# Nixie.net
KiCad netlist of a schematic drawn in Altium Designer
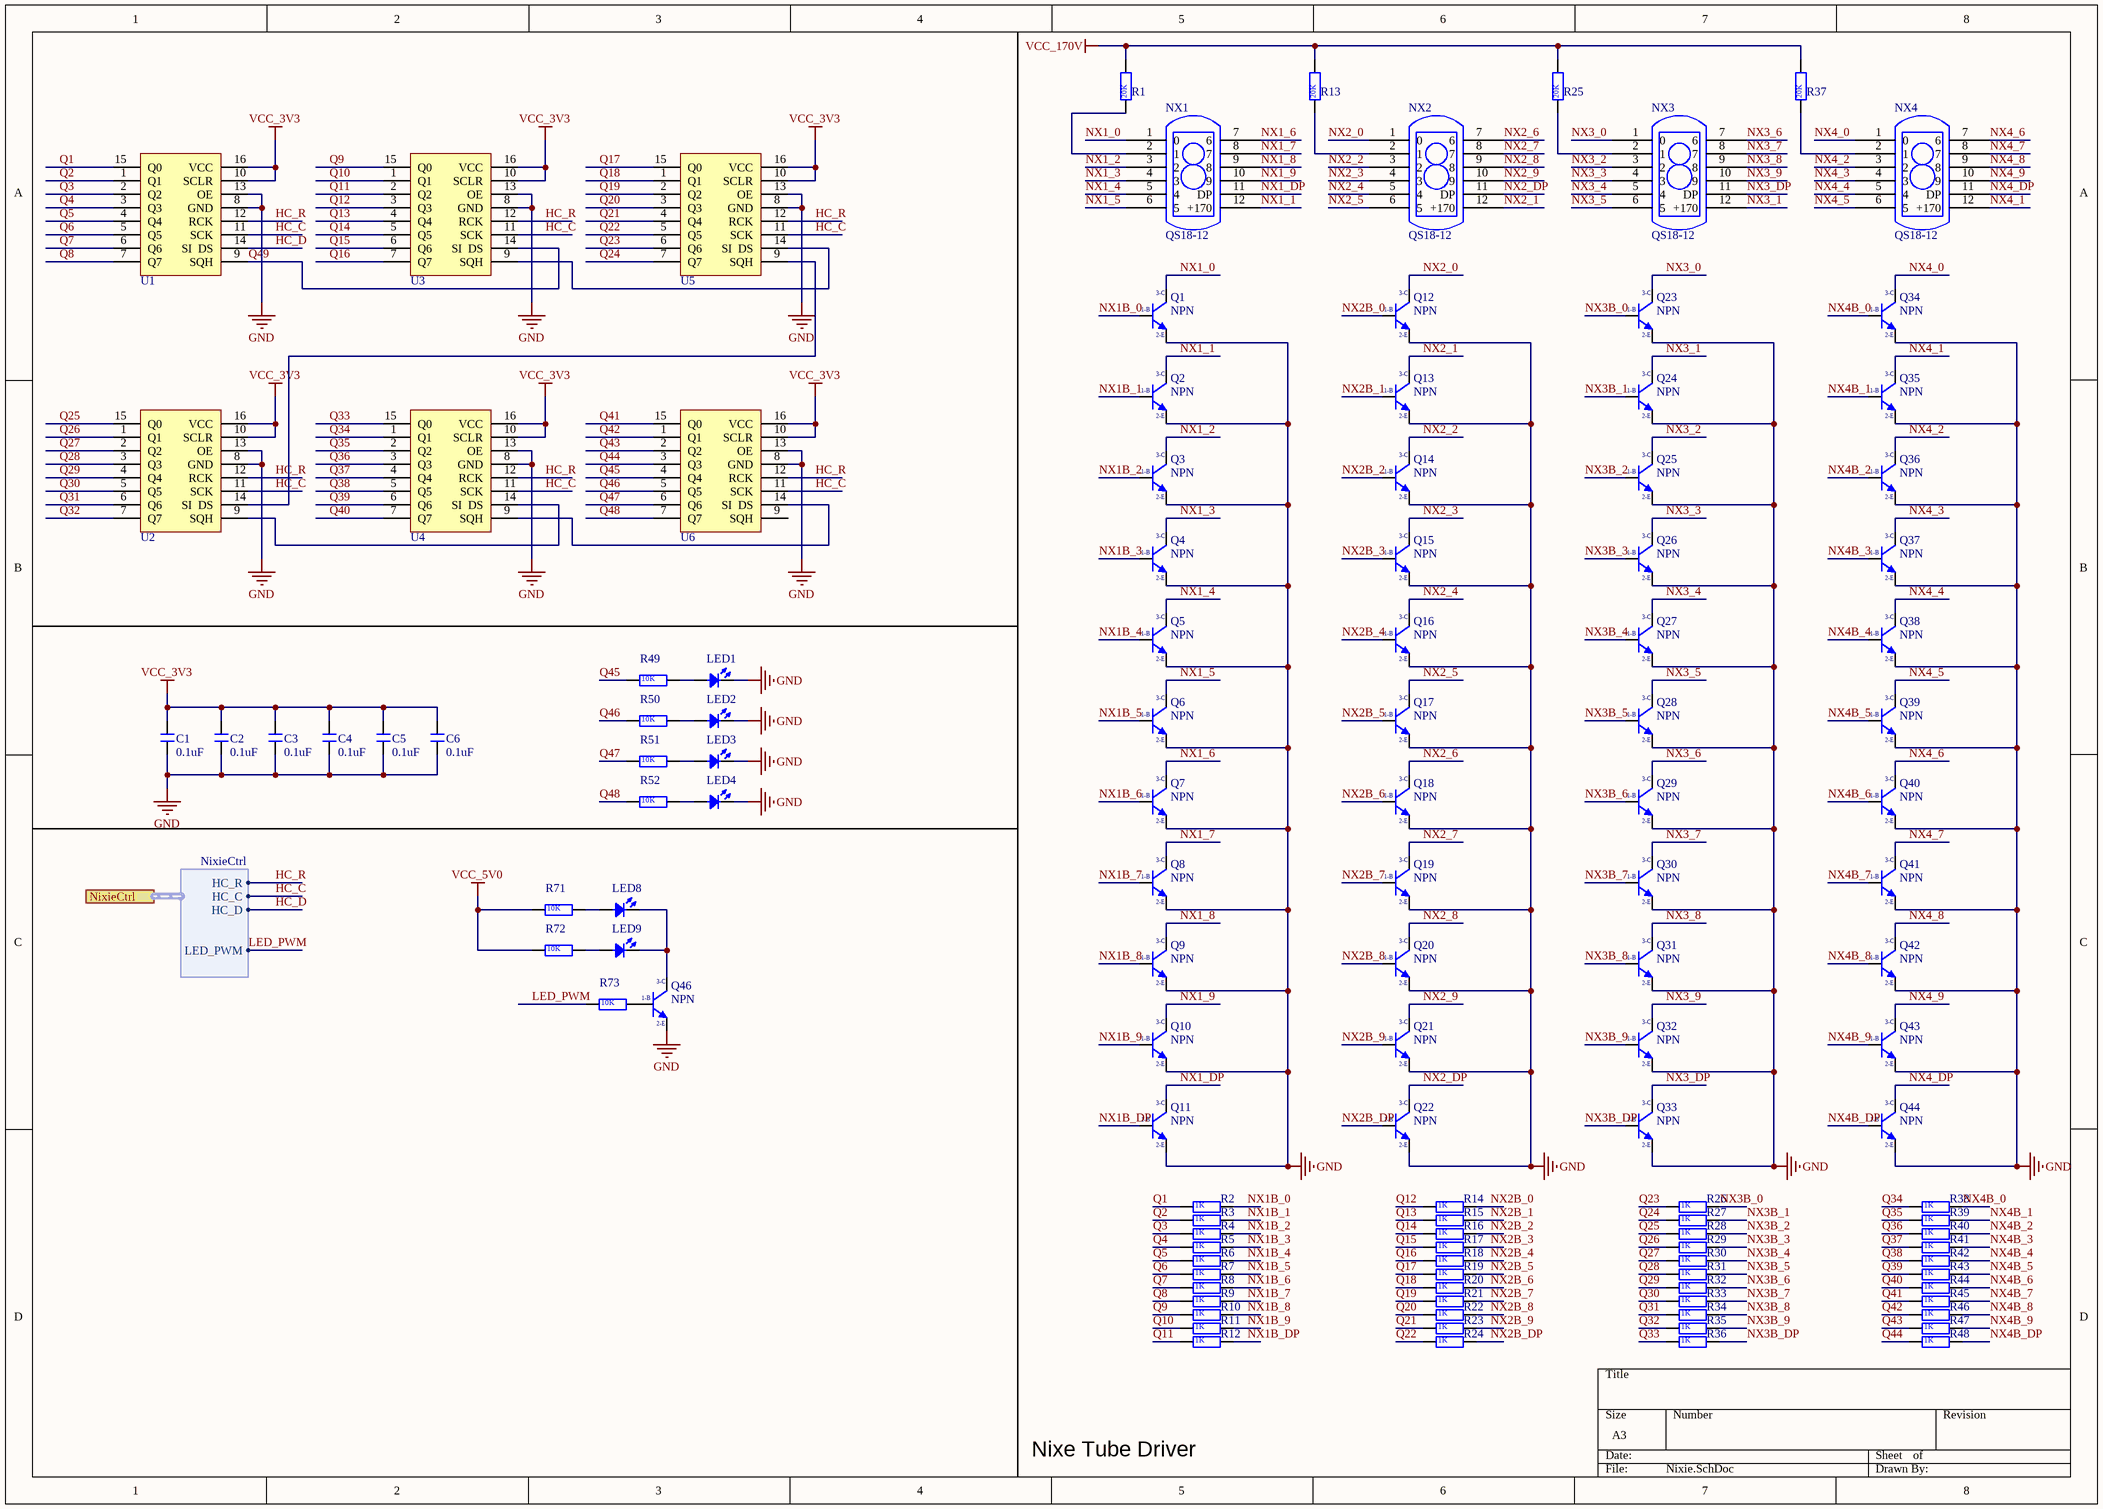
[diagram p0: Nixie.SchDoc]

(export (version "E")
  (design (tool "Eeschema 10.0.6"))
  (components
    (comp (ref "C1")
      (value "0.1uF")
      (footprint "C 0805")
      (description "无极性贴片电容")
      (fields (field (name "版权归属") "源创客"))
      (libsource (lib "电阻-电容-电感") (part "C"))
    )
    (comp (ref "C2")
      (value "0.1uF")
      (footprint "C 0805")
      (description "无极性贴片电容")
      (fields (field (name "版权归属") "源创客"))
      (libsource (lib "电阻-电容-电感") (part "C"))
    )
    (comp (ref "C3")
      (value "0.1uF")
      (footprint "C 0805")
      (description "无极性贴片电容")
      (fields (field (name "版权归属") "源创客"))
      (libsource (lib "电阻-电容-电感") (part "C"))
    )
    (comp (ref "C4")
      (value "0.1uF")
      (footprint "C 0805")
      (description "无极性贴片电容")
      (fields (field (name "版权归属") "源创客"))
      (libsource (lib "电阻-电容-电感") (part "C"))
    )
    (comp (ref "C5")
      (value "0.1uF")
      (footprint "C 0805")
      (description "无极性贴片电容")
      (fields (field (name "版权归属") "源创客"))
      (libsource (lib "电阻-电容-电感") (part "C"))
    )
    (comp (ref "C6")
      (value "0.1uF")
      (footprint "C 0805")
      (description "无极性贴片电容")
      (fields (field (name "版权归属") "源创客"))
      (libsource (lib "电阻-电容-电感") (part "C"))
    )
    (comp (ref "LED1")
      (value "LED")
      (footprint "0805D")
      (fields (field (name "PUBLISHER") "Altium Limited"))
      (libsource (lib "吴原理图库") (part "LED"))
    )
    (comp (ref "LED2")
      (value "LED")
      (footprint "0805D")
      (fields (field (name "PUBLISHER") "Altium Limited"))
      (libsource (lib "吴原理图库") (part "LED"))
    )
    (comp (ref "LED3")
      (value "LED")
      (footprint "0805D")
      (fields (field (name "PUBLISHER") "Altium Limited"))
      (libsource (lib "吴原理图库") (part "LED"))
    )
    (comp (ref "LED4")
      (value "LED")
      (footprint "0805D")
      (fields (field (name "PUBLISHER") "Altium Limited"))
      (libsource (lib "吴原理图库") (part "LED"))
    )
    (comp (ref "LED8")
      (value "LED")
      (footprint "LED 5MM-B")
      (fields (field (name "PUBLISHER") "Altium Limited"))
      (libsource (lib "吴原理图库") (part "LED"))
    )
    (comp (ref "LED9")
      (value "LED")
      (footprint "LED 5MM-B")
      (fields (field (name "PUBLISHER") "Altium Limited"))
      (libsource (lib "吴原理图库") (part "LED"))
    )
    (comp (ref "NX1")
      (value "QS18-12")
      (footprint "PCBComponent_1")
      (libsource (lib "Nixie") (part "QS18-12"))
    )
    (comp (ref "NX2")
      (value "QS18-12")
      (footprint "PCBComponent_1")
      (libsource (lib "Nixie") (part "QS18-12"))
    )
    (comp (ref "NX3")
      (value "QS18-12")
      (footprint "PCBComponent_1")
      (libsource (lib "Nixie") (part "QS18-12"))
    )
    (comp (ref "NX4")
      (value "QS18-12")
      (footprint "PCBComponent_1")
      (libsource (lib "Nixie") (part "QS18-12"))
    )
    (comp (ref "Q1") (value "NPN") (footprint "SOT-23") (libsource (lib "吴原理图库") (part "NPN-S8050-SOT-23")))
    (comp (ref "Q2") (value "NPN") (footprint "SOT-23") (libsource (lib "吴原理图库") (part "NPN-S8050-SOT-23")))
    (comp (ref "Q3") (value "NPN") (footprint "SOT-23") (libsource (lib "吴原理图库") (part "NPN-S8050-SOT-23")))
    (comp (ref "Q4") (value "NPN") (footprint "SOT-23") (libsource (lib "吴原理图库") (part "NPN-S8050-SOT-23")))
    (comp (ref "Q5") (value "NPN") (footprint "SOT-23") (libsource (lib "吴原理图库") (part "NPN-S8050-SOT-23")))
    (comp (ref "Q6") (value "NPN") (footprint "SOT-23") (libsource (lib "吴原理图库") (part "NPN-S8050-SOT-23")))
    (comp (ref "Q7") (value "NPN") (footprint "SOT-23") (libsource (lib "吴原理图库") (part "NPN-S8050-SOT-23")))
    (comp (ref "Q8") (value "NPN") (footprint "SOT-23") (libsource (lib "吴原理图库") (part "NPN-S8050-SOT-23")))
    (comp (ref "Q9") (value "NPN") (footprint "SOT-23") (libsource (lib "吴原理图库") (part "NPN-S8050-SOT-23")))
    (comp (ref "Q10") (value "NPN") (footprint "SOT-23") (libsource (lib "吴原理图库") (part "NPN-S8050-SOT-23")))
    (comp (ref "Q11") (value "NPN") (footprint "SOT-23") (libsource (lib "吴原理图库") (part "NPN-S8050-SOT-23")))
    (comp (ref "Q12") (value "NPN") (footprint "SOT-23") (libsource (lib "吴原理图库") (part "NPN-S8050-SOT-23")))
    (comp (ref "Q13") (value "NPN") (footprint "SOT-23") (libsource (lib "吴原理图库") (part "NPN-S8050-SOT-23")))
    (comp (ref "Q14") (value "NPN") (footprint "SOT-23") (libsource (lib "吴原理图库") (part "NPN-S8050-SOT-23")))
    (comp (ref "Q15") (value "NPN") (footprint "SOT-23") (libsource (lib "吴原理图库") (part "NPN-S8050-SOT-23")))
    (comp (ref "Q16") (value "NPN") (footprint "SOT-23") (libsource (lib "吴原理图库") (part "NPN-S8050-SOT-23")))
    (comp (ref "Q17") (value "NPN") (footprint "SOT-23") (libsource (lib "吴原理图库") (part "NPN-S8050-SOT-23")))
    (comp (ref "Q18") (value "NPN") (footprint "SOT-23") (libsource (lib "吴原理图库") (part "NPN-S8050-SOT-23")))
    (comp (ref "Q19") (value "NPN") (footprint "SOT-23") (libsource (lib "吴原理图库") (part "NPN-S8050-SOT-23")))
    (comp (ref "Q20") (value "NPN") (footprint "SOT-23") (libsource (lib "吴原理图库") (part "NPN-S8050-SOT-23")))
    (comp (ref "Q21") (value "NPN") (footprint "SOT-23") (libsource (lib "吴原理图库") (part "NPN-S8050-SOT-23")))
    (comp (ref "Q22") (value "NPN") (footprint "SOT-23") (libsource (lib "吴原理图库") (part "NPN-S8050-SOT-23")))
    (comp (ref "Q23") (value "NPN") (footprint "SOT-23") (libsource (lib "吴原理图库") (part "NPN-S8050-SOT-23")))
    (comp (ref "Q24") (value "NPN") (footprint "SOT-23") (libsource (lib "吴原理图库") (part "NPN-S8050-SOT-23")))
    (comp (ref "Q25") (value "NPN") (footprint "SOT-23") (libsource (lib "吴原理图库") (part "NPN-S8050-SOT-23")))
    (comp (ref "Q26") (value "NPN") (footprint "SOT-23") (libsource (lib "吴原理图库") (part "NPN-S8050-SOT-23")))
    (comp (ref "Q27") (value "NPN") (footprint "SOT-23") (libsource (lib "吴原理图库") (part "NPN-S8050-SOT-23")))
    (comp (ref "Q28") (value "NPN") (footprint "SOT-23") (libsource (lib "吴原理图库") (part "NPN-S8050-SOT-23")))
    (comp (ref "Q29") (value "NPN") (footprint "SOT-23") (libsource (lib "吴原理图库") (part "NPN-S8050-SOT-23")))
    (comp (ref "Q30") (value "NPN") (footprint "SOT-23") (libsource (lib "吴原理图库") (part "NPN-S8050-SOT-23")))
    (comp (ref "Q31") (value "NPN") (footprint "SOT-23") (libsource (lib "吴原理图库") (part "NPN-S8050-SOT-23")))
    (comp (ref "Q32") (value "NPN") (footprint "SOT-23") (libsource (lib "吴原理图库") (part "NPN-S8050-SOT-23")))
    (comp (ref "Q33") (value "NPN") (footprint "SOT-23") (libsource (lib "吴原理图库") (part "NPN-S8050-SOT-23")))
    (comp (ref "Q34") (value "NPN") (footprint "SOT-23") (libsource (lib "吴原理图库") (part "NPN-S8050-SOT-23")))
    (comp (ref "Q35") (value "NPN") (footprint "SOT-23") (libsource (lib "吴原理图库") (part "NPN-S8050-SOT-23")))
    (comp (ref "Q36") (value "NPN") (footprint "SOT-23") (libsource (lib "吴原理图库") (part "NPN-S8050-SOT-23")))
    (comp (ref "Q37") (value "NPN") (footprint "SOT-23") (libsource (lib "吴原理图库") (part "NPN-S8050-SOT-23")))
    (comp (ref "Q38") (value "NPN") (footprint "SOT-23") (libsource (lib "吴原理图库") (part "NPN-S8050-SOT-23")))
    (comp (ref "Q39") (value "NPN") (footprint "SOT-23") (libsource (lib "吴原理图库") (part "NPN-S8050-SOT-23")))
    (comp (ref "Q40") (value "NPN") (footprint "SOT-23") (libsource (lib "吴原理图库") (part "NPN-S8050-SOT-23")))
    (comp (ref "Q41") (value "NPN") (footprint "SOT-23") (libsource (lib "吴原理图库") (part "NPN-S8050-SOT-23")))
    (comp (ref "Q42") (value "NPN") (footprint "SOT-23") (libsource (lib "吴原理图库") (part "NPN-S8050-SOT-23")))
    (comp (ref "Q43") (value "NPN") (footprint "SOT-23") (libsource (lib "吴原理图库") (part "NPN-S8050-SOT-23")))
    (comp (ref "Q44") (value "NPN") (footprint "SOT-23") (libsource (lib "吴原理图库") (part "NPN-S8050-SOT-23")))
    (comp (ref "Q46") (value "NPN") (footprint "SOT-23") (libsource (lib "吴原理图库") (part "NPN-S8050-SOT-23")))
    (comp (ref "R1")
      (value "20K")
      (footprint "R 0603")
      (fields (field (name "Comment") "R"))
      (libsource (lib "") (part "R_1"))
    )
    (comp (ref "R2")
      (value "1K")
      (footprint "R 0603")
      (fields (field (name "Comment") "R"))
      (libsource (lib "吴原理图库") (part "R"))
    )
    (comp (ref "R3")
      (value "1K")
      (footprint "R 0603")
      (fields (field (name "Comment") "R"))
      (libsource (lib "吴原理图库") (part "R"))
    )
    (comp (ref "R4")
      (value "1K")
      (footprint "R 0603")
      (fields (field (name "Comment") "R"))
      (libsource (lib "吴原理图库") (part "R"))
    )
    (comp (ref "R5")
      (value "1K")
      (footprint "R 0603")
      (fields (field (name "Comment") "R"))
      (libsource (lib "吴原理图库") (part "R"))
    )
    (comp (ref "R6")
      (value "1K")
      (footprint "R 0603")
      (fields (field (name "Comment") "R"))
      (libsource (lib "吴原理图库") (part "R"))
    )
    (comp (ref "R7")
      (value "1K")
      (footprint "R 0603")
      (fields (field (name "Comment") "R"))
      (libsource (lib "吴原理图库") (part "R"))
    )
    (comp (ref "R8")
      (value "1K")
      (footprint "R 0603")
      (fields (field (name "Comment") "R"))
      (libsource (lib "吴原理图库") (part "R"))
    )
    (comp (ref "R9")
      (value "1K")
      (footprint "R 0603")
      (fields (field (name "Comment") "R"))
      (libsource (lib "吴原理图库") (part "R"))
    )
    (comp (ref "R10")
      (value "1K")
      (footprint "R 0603")
      (fields (field (name "Comment") "R"))
      (libsource (lib "吴原理图库") (part "R"))
    )
    (comp (ref "R11")
      (value "1K")
      (footprint "R 0603")
      (fields (field (name "Comment") "R"))
      (libsource (lib "吴原理图库") (part "R"))
    )
    (comp (ref "R12")
      (value "1K")
      (footprint "R 0603")
      (fields (field (name "Comment") "R"))
      (libsource (lib "吴原理图库") (part "R"))
    )
    (comp (ref "R13")
      (value "20K")
      (footprint "R 0603")
      (fields (field (name "Comment") "R"))
      (libsource (lib "") (part "R_1"))
    )
    (comp (ref "R14")
      (value "1K")
      (footprint "R 0603")
      (fields (field (name "Comment") "R"))
      (libsource (lib "吴原理图库") (part "R"))
    )
    (comp (ref "R15")
      (value "1K")
      (footprint "R 0603")
      (fields (field (name "Comment") "R"))
      (libsource (lib "吴原理图库") (part "R"))
    )
    (comp (ref "R16")
      (value "1K")
      (footprint "R 0603")
      (fields (field (name "Comment") "R"))
      (libsource (lib "吴原理图库") (part "R"))
    )
    (comp (ref "R17")
      (value "1K")
      (footprint "R 0603")
      (fields (field (name "Comment") "R"))
      (libsource (lib "吴原理图库") (part "R"))
    )
    (comp (ref "R18")
      (value "1K")
      (footprint "R 0603")
      (fields (field (name "Comment") "R"))
      (libsource (lib "吴原理图库") (part "R"))
    )
    (comp (ref "R19")
      (value "1K")
      (footprint "R 0603")
      (fields (field (name "Comment") "R"))
      (libsource (lib "吴原理图库") (part "R"))
    )
    (comp (ref "R20")
      (value "1K")
      (footprint "R 0603")
      (fields (field (name "Comment") "R"))
      (libsource (lib "吴原理图库") (part "R"))
    )
    (comp (ref "R21")
      (value "1K")
      (footprint "R 0603")
      (fields (field (name "Comment") "R"))
      (libsource (lib "吴原理图库") (part "R"))
    )
    (comp (ref "R22")
      (value "1K")
      (footprint "R 0603")
      (fields (field (name "Comment") "R"))
      (libsource (lib "吴原理图库") (part "R"))
    )
    (comp (ref "R23")
      (value "1K")
      (footprint "R 0603")
      (fields (field (name "Comment") "R"))
      (libsource (lib "吴原理图库") (part "R"))
    )
    (comp (ref "R24")
      (value "1K")
      (footprint "R 0603")
      (fields (field (name "Comment") "R"))
      (libsource (lib "吴原理图库") (part "R"))
    )
    (comp (ref "R25")
      (value "20K")
      (footprint "R 0603")
      (fields (field (name "Comment") "R"))
      (libsource (lib "") (part "R_1"))
    )
    (comp (ref "R26")
      (value "1K")
      (footprint "R 0603")
      (fields (field (name "Comment") "R"))
      (libsource (lib "吴原理图库") (part "R"))
    )
    (comp (ref "R27")
      (value "1K")
      (footprint "R 0603")
      (fields (field (name "Comment") "R"))
      (libsource (lib "吴原理图库") (part "R"))
    )
    (comp (ref "R28")
      (value "1K")
      (footprint "R 0603")
      (fields (field (name "Comment") "R"))
      (libsource (lib "吴原理图库") (part "R"))
    )
    (comp (ref "R29")
      (value "1K")
      (footprint "R 0603")
      (fields (field (name "Comment") "R"))
      (libsource (lib "吴原理图库") (part "R"))
    )
    (comp (ref "R30")
      (value "1K")
      (footprint "R 0603")
      (fields (field (name "Comment") "R"))
      (libsource (lib "吴原理图库") (part "R"))
    )
    (comp (ref "R31")
      (value "1K")
      (footprint "R 0603")
      (fields (field (name "Comment") "R"))
      (libsource (lib "吴原理图库") (part "R"))
    )
    (comp (ref "R32")
      (value "1K")
      (footprint "R 0603")
      (fields (field (name "Comment") "R"))
      (libsource (lib "吴原理图库") (part "R"))
    )
    (comp (ref "R33")
      (value "1K")
      (footprint "R 0603")
      (fields (field (name "Comment") "R"))
      (libsource (lib "吴原理图库") (part "R"))
    )
    (comp (ref "R34")
      (value "1K")
      (footprint "R 0603")
      (fields (field (name "Comment") "R"))
      (libsource (lib "吴原理图库") (part "R"))
    )
    (comp (ref "R35")
      (value "1K")
      (footprint "R 0603")
      (fields (field (name "Comment") "R"))
      (libsource (lib "吴原理图库") (part "R"))
    )
    (comp (ref "R36")
      (value "1K")
      (footprint "R 0603")
      (fields (field (name "Comment") "R"))
      (libsource (lib "吴原理图库") (part "R"))
    )
    (comp (ref "R37")
      (value "20K")
      (footprint "R 0603")
      (fields (field (name "Comment") "R"))
      (libsource (lib "") (part "R_1"))
    )
    (comp (ref "R38")
      (value "1K")
      (footprint "R 0603")
      (fields (field (name "Comment") "R"))
      (libsource (lib "吴原理图库") (part "R"))
    )
    (comp (ref "R39")
      (value "1K")
      (footprint "R 0603")
      (fields (field (name "Comment") "R"))
      (libsource (lib "吴原理图库") (part "R"))
    )
    (comp (ref "R40")
      (value "1K")
      (footprint "R 0603")
      (fields (field (name "Comment") "R"))
      (libsource (lib "吴原理图库") (part "R"))
    )
    (comp (ref "R41")
      (value "1K")
      (footprint "R 0603")
      (fields (field (name "Comment") "R"))
      (libsource (lib "吴原理图库") (part "R"))
    )
    (comp (ref "R42")
      (value "1K")
      (footprint "R 0603")
      (fields (field (name "Comment") "R"))
      (libsource (lib "吴原理图库") (part "R"))
    )
    (comp (ref "R43")
      (value "1K")
      (footprint "R 0603")
      (fields (field (name "Comment") "R"))
      (libsource (lib "吴原理图库") (part "R"))
    )
    (comp (ref "R44")
      (value "1K")
      (footprint "R 0603")
      (fields (field (name "Comment") "R"))
      (libsource (lib "吴原理图库") (part "R"))
    )
    (comp (ref "R45")
      (value "1K")
      (footprint "R 0603")
      (fields (field (name "Comment") "R"))
      (libsource (lib "吴原理图库") (part "R"))
    )
    (comp (ref "R46")
      (value "1K")
      (footprint "R 0603")
      (fields (field (name "Comment") "R"))
      (libsource (lib "吴原理图库") (part "R"))
    )
    (comp (ref "R47")
      (value "1K")
      (footprint "R 0603")
      (fields (field (name "Comment") "R"))
      (libsource (lib "吴原理图库") (part "R"))
    )
    (comp (ref "R48")
      (value "1K")
      (footprint "R 0603")
      (fields (field (name "Comment") "R"))
      (libsource (lib "吴原理图库") (part "R"))
    )
    (comp (ref "R49")
      (value "10K")
      (footprint "R 0603")
      (fields (field (name "Comment") "R"))
      (libsource (lib "吴原理图库") (part "R"))
    )
    (comp (ref "R50")
      (value "10K")
      (footprint "R 0603")
      (fields (field (name "Comment") "R"))
      (libsource (lib "吴原理图库") (part "R"))
    )
    (comp (ref "R51")
      (value "10K")
      (footprint "R 0603")
      (fields (field (name "Comment") "R"))
      (libsource (lib "吴原理图库") (part "R"))
    )
    (comp (ref "R52")
      (value "10K")
      (footprint "R 0603")
      (fields (field (name "Comment") "R"))
      (libsource (lib "吴原理图库") (part "R"))
    )
    (comp (ref "R71")
      (value "10K")
      (footprint "R 0603")
      (fields (field (name "Comment") "R"))
      (libsource (lib "吴原理图库") (part "R"))
    )
    (comp (ref "R72")
      (value "10K")
      (footprint "R 0603")
      (fields (field (name "Comment") "R"))
      (libsource (lib "吴原理图库") (part "R"))
    )
    (comp (ref "R73")
      (value "10K")
      (footprint "R 0603")
      (fields (field (name "Comment") "R"))
      (libsource (lib "吴原理图库") (part "R"))
    )
    (comp (ref "U1") (value "74HC595") (footprint "SOP16_M") (libsource (lib "吴原理图库") (part "74HC595_1")))
    (comp (ref "U2") (value "74HC595") (footprint "SOP16_M") (libsource (lib "吴原理图库") (part "74HC595_1")))
    (comp (ref "U3") (value "74HC595") (footprint "SOP16_M") (libsource (lib "吴原理图库") (part "74HC595_1")))
    (comp (ref "U4") (value "74HC595") (footprint "SOP16_M") (libsource (lib "吴原理图库") (part "74HC595_1")))
    (comp (ref "U5") (value "74HC595") (footprint "SOP16_M") (libsource (lib "吴原理图库") (part "74HC595_1")))
    (comp (ref "U6") (value "74HC595") (footprint "SOP16_M") (libsource (lib "吴原理图库") (part "74HC595_1")))
  )
  (nets
    (net (code "2") (name "/HC_C") (class "Default")
      (node (ref "U1") (pin "11") (pinfunction "SCK_11") (pintype "power_in"))
      (node (ref "U2") (pin "11") (pinfunction "SCK_11") (pintype "power_in"))
      (node (ref "U3") (pin "11") (pinfunction "SCK_11") (pintype "power_in"))
      (node (ref "U4") (pin "11") (pinfunction "SCK_11") (pintype "power_in"))
      (node (ref "U5") (pin "11") (pinfunction "SCK_11") (pintype "power_in"))
      (node (ref "U6") (pin "11") (pinfunction "SCK_11") (pintype "power_in"))
    )
    (net (code "3") (name "/HC_D") (class "Default")
      (node (ref "U1") (pin "14") (pinfunction "SI__DS_14") (pintype "power_in"))
    )
    (net (code "4") (name "/HC_R") (class "Default")
      (node (ref "U1") (pin "12") (pinfunction "RCK_12") (pintype "power_in"))
      (node (ref "U2") (pin "12") (pinfunction "RCK_12") (pintype "power_in"))
      (node (ref "U3") (pin "12") (pinfunction "RCK_12") (pintype "power_in"))
      (node (ref "U4") (pin "12") (pinfunction "RCK_12") (pintype "power_in"))
      (node (ref "U5") (pin "12") (pinfunction "RCK_12") (pintype "power_in"))
      (node (ref "U6") (pin "12") (pinfunction "RCK_12") (pintype "power_in"))
    )
    (net (code "5") (name "/LED_PWM") (class "Default")
      (node (ref "R73") (pin "1") (pinfunction "1_1") (pintype "passive"))
    )
    (net (code "6") (name "/NX1B_0") (class "Default")
      (node (ref "Q1") (pin "1") (pinfunction "B_1") (pintype "passive"))
      (node (ref "R2") (pin "2") (pinfunction "2_2") (pintype "passive"))
    )
    (net (code "7") (name "/NX1B_1") (class "Default")
      (node (ref "Q2") (pin "1") (pinfunction "B_1") (pintype "passive"))
      (node (ref "R3") (pin "2") (pinfunction "2_2") (pintype "passive"))
    )
    (net (code "8") (name "/NX1B_2") (class "Default")
      (node (ref "Q3") (pin "1") (pinfunction "B_1") (pintype "passive"))
      (node (ref "R4") (pin "2") (pinfunction "2_2") (pintype "passive"))
    )
    (net (code "9") (name "/NX1B_3") (class "Default")
      (node (ref "Q4") (pin "1") (pinfunction "B_1") (pintype "passive"))
      (node (ref "R5") (pin "2") (pinfunction "2_2") (pintype "passive"))
    )
    (net (code "10") (name "/NX1B_4") (class "Default")
      (node (ref "Q5") (pin "1") (pinfunction "B_1") (pintype "passive"))
      (node (ref "R6") (pin "2") (pinfunction "2_2") (pintype "passive"))
    )
    (net (code "11") (name "/NX1B_5") (class "Default")
      (node (ref "Q6") (pin "1") (pinfunction "B_1") (pintype "passive"))
      (node (ref "R7") (pin "2") (pinfunction "2_2") (pintype "passive"))
    )
    (net (code "12") (name "/NX1B_6") (class "Default")
      (node (ref "Q7") (pin "1") (pinfunction "B_1") (pintype "passive"))
      (node (ref "R8") (pin "2") (pinfunction "2_2") (pintype "passive"))
    )
    (net (code "13") (name "/NX1B_7") (class "Default")
      (node (ref "Q8") (pin "1") (pinfunction "B_1") (pintype "passive"))
      (node (ref "R9") (pin "2") (pinfunction "2_2") (pintype "passive"))
    )
    (net (code "14") (name "/NX1B_8") (class "Default")
      (node (ref "Q9") (pin "1") (pinfunction "B_1") (pintype "passive"))
      (node (ref "R10") (pin "2") (pinfunction "2_2") (pintype "passive"))
    )
    (net (code "15") (name "/NX1B_9") (class "Default")
      (node (ref "Q10") (pin "1") (pinfunction "B_1") (pintype "passive"))
      (node (ref "R11") (pin "2") (pinfunction "2_2") (pintype "passive"))
    )
    (net (code "16") (name "/NX1B_DP") (class "Default")
      (node (ref "Q11") (pin "1") (pinfunction "B_1") (pintype "passive"))
      (node (ref "R12") (pin "2") (pinfunction "2_2") (pintype "passive"))
    )
    (net (code "17") (name "/NX1_0") (class "Default")
      (node (ref "NX1") (pin "1") (pinfunction "0_1") (pintype "passive"))
      (node (ref "Q1") (pin "3") (pinfunction "C_3") (pintype "passive"))
    )
    (net (code "18") (name "/NX1_1") (class "Default")
      (node (ref "NX1") (pin "12") (pinfunction "+170_12") (pintype "passive"))
      (node (ref "Q2") (pin "3") (pinfunction "C_3") (pintype "passive"))
    )
    (net (code "19") (name "/NX1_2") (class "Default")
      (node (ref "NX1") (pin "3") (pinfunction "2_3") (pintype "passive"))
      (node (ref "Q3") (pin "3") (pinfunction "C_3") (pintype "passive"))
    )
    (net (code "20") (name "/NX1_3") (class "Default")
      (node (ref "NX1") (pin "4") (pinfunction "3_4") (pintype "passive"))
      (node (ref "Q4") (pin "3") (pinfunction "C_3") (pintype "passive"))
    )
    (net (code "21") (name "/NX1_4") (class "Default")
      (node (ref "NX1") (pin "5") (pinfunction "4_5") (pintype "passive"))
      (node (ref "Q5") (pin "3") (pinfunction "C_3") (pintype "passive"))
    )
    (net (code "22") (name "/NX1_5") (class "Default")
      (node (ref "NX1") (pin "6") (pinfunction "5_6") (pintype "passive"))
      (node (ref "Q6") (pin "3") (pinfunction "C_3") (pintype "passive"))
    )
    (net (code "23") (name "/NX1_6") (class "Default")
      (node (ref "NX1") (pin "7") (pinfunction "6_7") (pintype "passive"))
      (node (ref "Q7") (pin "3") (pinfunction "C_3") (pintype "passive"))
    )
    (net (code "24") (name "/NX1_7") (class "Default")
      (node (ref "NX1") (pin "8") (pinfunction "7_8") (pintype "passive"))
      (node (ref "Q8") (pin "3") (pinfunction "C_3") (pintype "passive"))
    )
    (net (code "25") (name "/NX1_8") (class "Default")
      (node (ref "NX1") (pin "9") (pinfunction "8_9") (pintype "passive"))
      (node (ref "Q9") (pin "3") (pinfunction "C_3") (pintype "passive"))
    )
    (net (code "26") (name "/NX1_9") (class "Default")
      (node (ref "NX1") (pin "10") (pinfunction "9_10") (pintype "passive"))
      (node (ref "Q10") (pin "3") (pinfunction "C_3") (pintype "passive"))
    )
    (net (code "27") (name "/NX1_DP") (class "Default")
      (node (ref "NX1") (pin "11") (pinfunction "DP_11") (pintype "passive"))
      (node (ref "Q11") (pin "3") (pinfunction "C_3") (pintype "passive"))
    )
    (net (code "28") (name "/NX2B_0") (class "Default")
      (node (ref "Q12") (pin "1") (pinfunction "B_1") (pintype "passive"))
      (node (ref "R14") (pin "2") (pinfunction "2_2") (pintype "passive"))
    )
    (net (code "29") (name "/NX2B_1") (class "Default")
      (node (ref "Q13") (pin "1") (pinfunction "B_1") (pintype "passive"))
      (node (ref "R15") (pin "2") (pinfunction "2_2") (pintype "passive"))
    )
    (net (code "30") (name "/NX2B_2") (class "Default")
      (node (ref "Q14") (pin "1") (pinfunction "B_1") (pintype "passive"))
      (node (ref "R16") (pin "2") (pinfunction "2_2") (pintype "passive"))
    )
    (net (code "31") (name "/NX2B_3") (class "Default")
      (node (ref "Q15") (pin "1") (pinfunction "B_1") (pintype "passive"))
      (node (ref "R17") (pin "2") (pinfunction "2_2") (pintype "passive"))
    )
    (net (code "32") (name "/NX2B_4") (class "Default")
      (node (ref "Q16") (pin "1") (pinfunction "B_1") (pintype "passive"))
      (node (ref "R18") (pin "2") (pinfunction "2_2") (pintype "passive"))
    )
    (net (code "33") (name "/NX2B_5") (class "Default")
      (node (ref "Q17") (pin "1") (pinfunction "B_1") (pintype "passive"))
      (node (ref "R19") (pin "2") (pinfunction "2_2") (pintype "passive"))
    )
    (net (code "34") (name "/NX2B_6") (class "Default")
      (node (ref "Q18") (pin "1") (pinfunction "B_1") (pintype "passive"))
      (node (ref "R20") (pin "2") (pinfunction "2_2") (pintype "passive"))
    )
    (net (code "35") (name "/NX2B_7") (class "Default")
      (node (ref "Q19") (pin "1") (pinfunction "B_1") (pintype "passive"))
      (node (ref "R21") (pin "2") (pinfunction "2_2") (pintype "passive"))
    )
    (net (code "36") (name "/NX2B_8") (class "Default")
      (node (ref "Q20") (pin "1") (pinfunction "B_1") (pintype "passive"))
      (node (ref "R22") (pin "2") (pinfunction "2_2") (pintype "passive"))
    )
    (net (code "37") (name "/NX2B_9") (class "Default")
      (node (ref "Q21") (pin "1") (pinfunction "B_1") (pintype "passive"))
      (node (ref "R23") (pin "2") (pinfunction "2_2") (pintype "passive"))
    )
    (net (code "38") (name "/NX2B_DP") (class "Default")
      (node (ref "Q22") (pin "1") (pinfunction "B_1") (pintype "passive"))
      (node (ref "R24") (pin "2") (pinfunction "2_2") (pintype "passive"))
    )
    (net (code "39") (name "/NX2_0") (class "Default")
      (node (ref "NX2") (pin "1") (pinfunction "0_1") (pintype "passive"))
      (node (ref "Q12") (pin "3") (pinfunction "C_3") (pintype "passive"))
    )
    (net (code "40") (name "/NX2_1") (class "Default")
      (node (ref "NX2") (pin "12") (pinfunction "+170_12") (pintype "passive"))
      (node (ref "Q13") (pin "3") (pinfunction "C_3") (pintype "passive"))
    )
    (net (code "41") (name "/NX2_2") (class "Default")
      (node (ref "NX2") (pin "3") (pinfunction "2_3") (pintype "passive"))
      (node (ref "Q14") (pin "3") (pinfunction "C_3") (pintype "passive"))
    )
    (net (code "42") (name "/NX2_3") (class "Default")
      (node (ref "NX2") (pin "4") (pinfunction "3_4") (pintype "passive"))
      (node (ref "Q15") (pin "3") (pinfunction "C_3") (pintype "passive"))
    )
    (net (code "43") (name "/NX2_4") (class "Default")
      (node (ref "NX2") (pin "5") (pinfunction "4_5") (pintype "passive"))
      (node (ref "Q16") (pin "3") (pinfunction "C_3") (pintype "passive"))
    )
    (net (code "44") (name "/NX2_5") (class "Default")
      (node (ref "NX2") (pin "6") (pinfunction "5_6") (pintype "passive"))
      (node (ref "Q17") (pin "3") (pinfunction "C_3") (pintype "passive"))
    )
    (net (code "45") (name "/NX2_6") (class "Default")
      (node (ref "NX2") (pin "7") (pinfunction "6_7") (pintype "passive"))
      (node (ref "Q18") (pin "3") (pinfunction "C_3") (pintype "passive"))
    )
    (net (code "46") (name "/NX2_7") (class "Default")
      (node (ref "NX2") (pin "8") (pinfunction "7_8") (pintype "passive"))
      (node (ref "Q19") (pin "3") (pinfunction "C_3") (pintype "passive"))
    )
    (net (code "47") (name "/NX2_8") (class "Default")
      (node (ref "NX2") (pin "9") (pinfunction "8_9") (pintype "passive"))
      (node (ref "Q20") (pin "3") (pinfunction "C_3") (pintype "passive"))
    )
    (net (code "48") (name "/NX2_9") (class "Default")
      (node (ref "NX2") (pin "10") (pinfunction "9_10") (pintype "passive"))
      (node (ref "Q21") (pin "3") (pinfunction "C_3") (pintype "passive"))
    )
    (net (code "49") (name "/NX2_DP") (class "Default")
      (node (ref "NX2") (pin "11") (pinfunction "DP_11") (pintype "passive"))
      (node (ref "Q22") (pin "3") (pinfunction "C_3") (pintype "passive"))
    )
    (net (code "50") (name "/NX3B_0") (class "Default")
      (node (ref "Q23") (pin "1") (pinfunction "B_1") (pintype "passive"))
      (node (ref "R26") (pin "2") (pinfunction "2_2") (pintype "passive"))
    )
    (net (code "51") (name "/NX3B_1") (class "Default")
      (node (ref "Q24") (pin "1") (pinfunction "B_1") (pintype "passive"))
      (node (ref "R27") (pin "2") (pinfunction "2_2") (pintype "passive"))
    )
    (net (code "52") (name "/NX3B_2") (class "Default")
      (node (ref "Q25") (pin "1") (pinfunction "B_1") (pintype "passive"))
      (node (ref "R28") (pin "2") (pinfunction "2_2") (pintype "passive"))
    )
    (net (code "53") (name "/NX3B_3") (class "Default")
      (node (ref "Q26") (pin "1") (pinfunction "B_1") (pintype "passive"))
      (node (ref "R29") (pin "2") (pinfunction "2_2") (pintype "passive"))
    )
    (net (code "54") (name "/NX3B_4") (class "Default")
      (node (ref "Q27") (pin "1") (pinfunction "B_1") (pintype "passive"))
      (node (ref "R30") (pin "2") (pinfunction "2_2") (pintype "passive"))
    )
    (net (code "55") (name "/NX3B_5") (class "Default")
      (node (ref "Q28") (pin "1") (pinfunction "B_1") (pintype "passive"))
      (node (ref "R31") (pin "2") (pinfunction "2_2") (pintype "passive"))
    )
    (net (code "56") (name "/NX3B_6") (class "Default")
      (node (ref "Q29") (pin "1") (pinfunction "B_1") (pintype "passive"))
      (node (ref "R32") (pin "2") (pinfunction "2_2") (pintype "passive"))
    )
    (net (code "57") (name "/NX3B_7") (class "Default")
      (node (ref "Q30") (pin "1") (pinfunction "B_1") (pintype "passive"))
      (node (ref "R33") (pin "2") (pinfunction "2_2") (pintype "passive"))
    )
    (net (code "58") (name "/NX3B_8") (class "Default")
      (node (ref "Q31") (pin "1") (pinfunction "B_1") (pintype "passive"))
      (node (ref "R34") (pin "2") (pinfunction "2_2") (pintype "passive"))
    )
    (net (code "59") (name "/NX3B_9") (class "Default")
      (node (ref "Q32") (pin "1") (pinfunction "B_1") (pintype "passive"))
      (node (ref "R35") (pin "2") (pinfunction "2_2") (pintype "passive"))
    )
    (net (code "60") (name "/NX3B_DP") (class "Default")
      (node (ref "Q33") (pin "1") (pinfunction "B_1") (pintype "passive"))
      (node (ref "R36") (pin "2") (pinfunction "2_2") (pintype "passive"))
    )
    (net (code "61") (name "/NX3_0") (class "Default")
      (node (ref "NX3") (pin "1") (pinfunction "0_1") (pintype "passive"))
      (node (ref "Q23") (pin "3") (pinfunction "C_3") (pintype "passive"))
    )
    (net (code "62") (name "/NX3_1") (class "Default")
      (node (ref "NX3") (pin "12") (pinfunction "+170_12") (pintype "passive"))
      (node (ref "Q24") (pin "3") (pinfunction "C_3") (pintype "passive"))
    )
    (net (code "63") (name "/NX3_2") (class "Default")
      (node (ref "NX3") (pin "3") (pinfunction "2_3") (pintype "passive"))
      (node (ref "Q25") (pin "3") (pinfunction "C_3") (pintype "passive"))
    )
    (net (code "64") (name "/NX3_3") (class "Default")
      (node (ref "NX3") (pin "4") (pinfunction "3_4") (pintype "passive"))
      (node (ref "Q26") (pin "3") (pinfunction "C_3") (pintype "passive"))
    )
    (net (code "65") (name "/NX3_4") (class "Default")
      (node (ref "NX3") (pin "5") (pinfunction "4_5") (pintype "passive"))
      (node (ref "Q27") (pin "3") (pinfunction "C_3") (pintype "passive"))
    )
    (net (code "66") (name "/NX3_5") (class "Default")
      (node (ref "NX3") (pin "6") (pinfunction "5_6") (pintype "passive"))
      (node (ref "Q28") (pin "3") (pinfunction "C_3") (pintype "passive"))
    )
    (net (code "67") (name "/NX3_6") (class "Default")
      (node (ref "NX3") (pin "7") (pinfunction "6_7") (pintype "passive"))
      (node (ref "Q29") (pin "3") (pinfunction "C_3") (pintype "passive"))
    )
    (net (code "68") (name "/NX3_7") (class "Default")
      (node (ref "NX3") (pin "8") (pinfunction "7_8") (pintype "passive"))
      (node (ref "Q30") (pin "3") (pinfunction "C_3") (pintype "passive"))
    )
    (net (code "69") (name "/NX3_8") (class "Default")
      (node (ref "NX3") (pin "9") (pinfunction "8_9") (pintype "passive"))
      (node (ref "Q31") (pin "3") (pinfunction "C_3") (pintype "passive"))
    )
    (net (code "70") (name "/NX3_9") (class "Default")
      (node (ref "NX3") (pin "10") (pinfunction "9_10") (pintype "passive"))
      (node (ref "Q32") (pin "3") (pinfunction "C_3") (pintype "passive"))
    )
    (net (code "71") (name "/NX3_DP") (class "Default")
      (node (ref "NX3") (pin "11") (pinfunction "DP_11") (pintype "passive"))
      (node (ref "Q33") (pin "3") (pinfunction "C_3") (pintype "passive"))
    )
    (net (code "72") (name "/NX4B_0") (class "Default")
      (node (ref "Q34") (pin "1") (pinfunction "B_1") (pintype "passive"))
      (node (ref "R38") (pin "2") (pinfunction "2_2") (pintype "passive"))
    )
    (net (code "73") (name "/NX4B_1") (class "Default")
      (node (ref "Q35") (pin "1") (pinfunction "B_1") (pintype "passive"))
      (node (ref "R39") (pin "2") (pinfunction "2_2") (pintype "passive"))
    )
    (net (code "74") (name "/NX4B_2") (class "Default")
      (node (ref "Q36") (pin "1") (pinfunction "B_1") (pintype "passive"))
      (node (ref "R40") (pin "2") (pinfunction "2_2") (pintype "passive"))
    )
    (net (code "75") (name "/NX4B_3") (class "Default")
      (node (ref "Q37") (pin "1") (pinfunction "B_1") (pintype "passive"))
      (node (ref "R41") (pin "2") (pinfunction "2_2") (pintype "passive"))
    )
    (net (code "76") (name "/NX4B_4") (class "Default")
      (node (ref "Q38") (pin "1") (pinfunction "B_1") (pintype "passive"))
      (node (ref "R42") (pin "2") (pinfunction "2_2") (pintype "passive"))
    )
    (net (code "77") (name "/NX4B_5") (class "Default")
      (node (ref "Q39") (pin "1") (pinfunction "B_1") (pintype "passive"))
      (node (ref "R43") (pin "2") (pinfunction "2_2") (pintype "passive"))
    )
    (net (code "78") (name "/NX4B_6") (class "Default")
      (node (ref "Q40") (pin "1") (pinfunction "B_1") (pintype "passive"))
      (node (ref "R44") (pin "2") (pinfunction "2_2") (pintype "passive"))
    )
    (net (code "79") (name "/NX4B_7") (class "Default")
      (node (ref "Q41") (pin "1") (pinfunction "B_1") (pintype "passive"))
      (node (ref "R45") (pin "2") (pinfunction "2_2") (pintype "passive"))
    )
    (net (code "80") (name "/NX4B_8") (class "Default")
      (node (ref "Q42") (pin "1") (pinfunction "B_1") (pintype "passive"))
      (node (ref "R46") (pin "2") (pinfunction "2_2") (pintype "passive"))
    )
    (net (code "81") (name "/NX4B_9") (class "Default")
      (node (ref "Q43") (pin "1") (pinfunction "B_1") (pintype "passive"))
      (node (ref "R47") (pin "2") (pinfunction "2_2") (pintype "passive"))
    )
    (net (code "82") (name "/NX4B_DP") (class "Default")
      (node (ref "Q44") (pin "1") (pinfunction "B_1") (pintype "passive"))
      (node (ref "R48") (pin "2") (pinfunction "2_2") (pintype "passive"))
    )
    (net (code "83") (name "/NX4_0") (class "Default")
      (node (ref "NX4") (pin "1") (pinfunction "0_1") (pintype "passive"))
      (node (ref "Q34") (pin "3") (pinfunction "C_3") (pintype "passive"))
    )
    (net (code "84") (name "/NX4_1") (class "Default")
      (node (ref "NX4") (pin "12") (pinfunction "+170_12") (pintype "passive"))
      (node (ref "Q35") (pin "3") (pinfunction "C_3") (pintype "passive"))
    )
    (net (code "85") (name "/NX4_2") (class "Default")
      (node (ref "NX4") (pin "3") (pinfunction "2_3") (pintype "passive"))
      (node (ref "Q36") (pin "3") (pinfunction "C_3") (pintype "passive"))
    )
    (net (code "86") (name "/NX4_3") (class "Default")
      (node (ref "NX4") (pin "4") (pinfunction "3_4") (pintype "passive"))
      (node (ref "Q37") (pin "3") (pinfunction "C_3") (pintype "passive"))
    )
    (net (code "87") (name "/NX4_4") (class "Default")
      (node (ref "NX4") (pin "5") (pinfunction "4_5") (pintype "passive"))
      (node (ref "Q38") (pin "3") (pinfunction "C_3") (pintype "passive"))
    )
    (net (code "88") (name "/NX4_5") (class "Default")
      (node (ref "NX4") (pin "6") (pinfunction "5_6") (pintype "passive"))
      (node (ref "Q39") (pin "3") (pinfunction "C_3") (pintype "passive"))
    )
    (net (code "89") (name "/NX4_6") (class "Default")
      (node (ref "NX4") (pin "7") (pinfunction "6_7") (pintype "passive"))
      (node (ref "Q40") (pin "3") (pinfunction "C_3") (pintype "passive"))
    )
    (net (code "90") (name "/NX4_7") (class "Default")
      (node (ref "NX4") (pin "8") (pinfunction "7_8") (pintype "passive"))
      (node (ref "Q41") (pin "3") (pinfunction "C_3") (pintype "passive"))
    )
    (net (code "91") (name "/NX4_8") (class "Default")
      (node (ref "NX4") (pin "9") (pinfunction "8_9") (pintype "passive"))
      (node (ref "Q42") (pin "3") (pinfunction "C_3") (pintype "passive"))
    )
    (net (code "92") (name "/NX4_9") (class "Default")
      (node (ref "NX4") (pin "10") (pinfunction "9_10") (pintype "passive"))
      (node (ref "Q43") (pin "3") (pinfunction "C_3") (pintype "passive"))
    )
    (net (code "93") (name "/NX4_DP") (class "Default")
      (node (ref "NX4") (pin "11") (pinfunction "DP_11") (pintype "passive"))
      (node (ref "Q44") (pin "3") (pinfunction "C_3") (pintype "passive"))
    )
    (net (code "94") (name "/Q1") (class "Default")
      (node (ref "R2") (pin "1") (pinfunction "1_1") (pintype "passive"))
      (node (ref "U1") (pin "15") (pinfunction "Q0_15") (pintype "power_in"))
    )
    (net (code "95") (name "/Q2") (class "Default")
      (node (ref "R3") (pin "1") (pinfunction "1_1") (pintype "passive"))
      (node (ref "U1") (pin "1") (pinfunction "Q1_1") (pintype "power_in"))
    )
    (net (code "96") (name "/Q3") (class "Default")
      (node (ref "R4") (pin "1") (pinfunction "1_1") (pintype "passive"))
      (node (ref "U1") (pin "2") (pinfunction "Q2_2") (pintype "power_in"))
    )
    (net (code "97") (name "/Q4") (class "Default")
      (node (ref "R5") (pin "1") (pinfunction "1_1") (pintype "passive"))
      (node (ref "U1") (pin "3") (pinfunction "Q3_3") (pintype "power_in"))
    )
    (net (code "98") (name "/Q5") (class "Default")
      (node (ref "R6") (pin "1") (pinfunction "1_1") (pintype "passive"))
      (node (ref "U1") (pin "4") (pinfunction "Q4_4") (pintype "power_in"))
    )
    (net (code "99") (name "/Q6") (class "Default")
      (node (ref "R7") (pin "1") (pinfunction "1_1") (pintype "passive"))
      (node (ref "U1") (pin "5") (pinfunction "Q5_5") (pintype "power_in"))
    )
    (net (code "100") (name "/Q7") (class "Default")
      (node (ref "R8") (pin "1") (pinfunction "1_1") (pintype "passive"))
      (node (ref "U1") (pin "6") (pinfunction "Q6_6") (pintype "power_in"))
    )
    (net (code "101") (name "/Q8") (class "Default")
      (node (ref "R9") (pin "1") (pinfunction "1_1") (pintype "passive"))
      (node (ref "U1") (pin "7") (pinfunction "Q7_7") (pintype "power_in"))
    )
    (net (code "102") (name "/Q9") (class "Default")
      (node (ref "R10") (pin "1") (pinfunction "1_1") (pintype "passive"))
      (node (ref "U3") (pin "15") (pinfunction "Q0_15") (pintype "power_in"))
    )
    (net (code "103") (name "/Q10") (class "Default")
      (node (ref "R11") (pin "1") (pinfunction "1_1") (pintype "passive"))
      (node (ref "U3") (pin "1") (pinfunction "Q1_1") (pintype "power_in"))
    )
    (net (code "104") (name "/Q11") (class "Default")
      (node (ref "R12") (pin "1") (pinfunction "1_1") (pintype "passive"))
      (node (ref "U3") (pin "2") (pinfunction "Q2_2") (pintype "power_in"))
    )
    (net (code "105") (name "/Q12") (class "Default")
      (node (ref "R14") (pin "1") (pinfunction "1_1") (pintype "passive"))
      (node (ref "U3") (pin "3") (pinfunction "Q3_3") (pintype "power_in"))
    )
    (net (code "106") (name "/Q13") (class "Default")
      (node (ref "R15") (pin "1") (pinfunction "1_1") (pintype "passive"))
      (node (ref "U3") (pin "4") (pinfunction "Q4_4") (pintype "power_in"))
    )
    (net (code "107") (name "/Q14") (class "Default")
      (node (ref "R16") (pin "1") (pinfunction "1_1") (pintype "passive"))
      (node (ref "U3") (pin "5") (pinfunction "Q5_5") (pintype "power_in"))
    )
    (net (code "108") (name "/Q15") (class "Default")
      (node (ref "R17") (pin "1") (pinfunction "1_1") (pintype "passive"))
      (node (ref "U3") (pin "6") (pinfunction "Q6_6") (pintype "power_in"))
    )
    (net (code "109") (name "/Q16") (class "Default")
      (node (ref "R18") (pin "1") (pinfunction "1_1") (pintype "passive"))
      (node (ref "U3") (pin "7") (pinfunction "Q7_7") (pintype "power_in"))
    )
    (net (code "110") (name "/Q17") (class "Default")
      (node (ref "R19") (pin "1") (pinfunction "1_1") (pintype "passive"))
      (node (ref "U5") (pin "15") (pinfunction "Q0_15") (pintype "power_in"))
    )
    (net (code "111") (name "/Q18") (class "Default")
      (node (ref "R20") (pin "1") (pinfunction "1_1") (pintype "passive"))
      (node (ref "U5") (pin "1") (pinfunction "Q1_1") (pintype "power_in"))
    )
    (net (code "112") (name "/Q19") (class "Default")
      (node (ref "R21") (pin "1") (pinfunction "1_1") (pintype "passive"))
      (node (ref "U5") (pin "2") (pinfunction "Q2_2") (pintype "power_in"))
    )
    (net (code "113") (name "/Q20") (class "Default")
      (node (ref "R22") (pin "1") (pinfunction "1_1") (pintype "passive"))
      (node (ref "U5") (pin "3") (pinfunction "Q3_3") (pintype "power_in"))
    )
    (net (code "114") (name "/Q21") (class "Default")
      (node (ref "R23") (pin "1") (pinfunction "1_1") (pintype "passive"))
      (node (ref "U5") (pin "4") (pinfunction "Q4_4") (pintype "power_in"))
    )
    (net (code "115") (name "/Q22") (class "Default")
      (node (ref "R24") (pin "1") (pinfunction "1_1") (pintype "passive"))
      (node (ref "U5") (pin "5") (pinfunction "Q5_5") (pintype "power_in"))
    )
    (net (code "116") (name "/Q23") (class "Default")
      (node (ref "R26") (pin "1") (pinfunction "1_1") (pintype "passive"))
      (node (ref "U5") (pin "6") (pinfunction "Q6_6") (pintype "power_in"))
    )
    (net (code "117") (name "/Q24") (class "Default")
      (node (ref "R27") (pin "1") (pinfunction "1_1") (pintype "passive"))
      (node (ref "U5") (pin "7") (pinfunction "Q7_7") (pintype "power_in"))
    )
    (net (code "118") (name "/Q25") (class "Default")
      (node (ref "R28") (pin "1") (pinfunction "1_1") (pintype "passive"))
      (node (ref "U2") (pin "15") (pinfunction "Q0_15") (pintype "power_in"))
    )
    (net (code "119") (name "/Q26") (class "Default")
      (node (ref "R29") (pin "1") (pinfunction "1_1") (pintype "passive"))
      (node (ref "U2") (pin "1") (pinfunction "Q1_1") (pintype "power_in"))
    )
    (net (code "120") (name "/Q27") (class "Default")
      (node (ref "R30") (pin "1") (pinfunction "1_1") (pintype "passive"))
      (node (ref "U2") (pin "2") (pinfunction "Q2_2") (pintype "power_in"))
    )
    (net (code "121") (name "/Q28") (class "Default")
      (node (ref "R31") (pin "1") (pinfunction "1_1") (pintype "passive"))
      (node (ref "U2") (pin "3") (pinfunction "Q3_3") (pintype "power_in"))
    )
    (net (code "122") (name "/Q29") (class "Default")
      (node (ref "R32") (pin "1") (pinfunction "1_1") (pintype "passive"))
      (node (ref "U2") (pin "4") (pinfunction "Q4_4") (pintype "power_in"))
    )
    (net (code "123") (name "/Q30") (class "Default")
      (node (ref "R33") (pin "1") (pinfunction "1_1") (pintype "passive"))
      (node (ref "U2") (pin "5") (pinfunction "Q5_5") (pintype "power_in"))
    )
    (net (code "124") (name "/Q31") (class "Default")
      (node (ref "R34") (pin "1") (pinfunction "1_1") (pintype "passive"))
      (node (ref "U2") (pin "6") (pinfunction "Q6_6") (pintype "power_in"))
    )
    (net (code "125") (name "/Q32") (class "Default")
      (node (ref "R35") (pin "1") (pinfunction "1_1") (pintype "passive"))
      (node (ref "U2") (pin "7") (pinfunction "Q7_7") (pintype "power_in"))
    )
    (net (code "126") (name "/Q33") (class "Default")
      (node (ref "R36") (pin "1") (pinfunction "1_1") (pintype "passive"))
      (node (ref "U4") (pin "15") (pinfunction "Q0_15") (pintype "power_in"))
    )
    (net (code "127") (name "/Q34") (class "Default")
      (node (ref "R38") (pin "1") (pinfunction "1_1") (pintype "passive"))
      (node (ref "U4") (pin "1") (pinfunction "Q1_1") (pintype "power_in"))
    )
    (net (code "128") (name "/Q35") (class "Default")
      (node (ref "R39") (pin "1") (pinfunction "1_1") (pintype "passive"))
      (node (ref "U4") (pin "2") (pinfunction "Q2_2") (pintype "power_in"))
    )
    (net (code "129") (name "/Q36") (class "Default")
      (node (ref "R40") (pin "1") (pinfunction "1_1") (pintype "passive"))
      (node (ref "U4") (pin "3") (pinfunction "Q3_3") (pintype "power_in"))
    )
    (net (code "130") (name "/Q37") (class "Default")
      (node (ref "R41") (pin "1") (pinfunction "1_1") (pintype "passive"))
      (node (ref "U4") (pin "4") (pinfunction "Q4_4") (pintype "power_in"))
    )
    (net (code "131") (name "/Q38") (class "Default")
      (node (ref "R42") (pin "1") (pinfunction "1_1") (pintype "passive"))
      (node (ref "U4") (pin "5") (pinfunction "Q5_5") (pintype "power_in"))
    )
    (net (code "132") (name "/Q39") (class "Default")
      (node (ref "R43") (pin "1") (pinfunction "1_1") (pintype "passive"))
      (node (ref "U4") (pin "6") (pinfunction "Q6_6") (pintype "power_in"))
    )
    (net (code "133") (name "/Q40") (class "Default")
      (node (ref "R44") (pin "1") (pinfunction "1_1") (pintype "passive"))
      (node (ref "U4") (pin "7") (pinfunction "Q7_7") (pintype "power_in"))
    )
    (net (code "134") (name "/Q41") (class "Default")
      (node (ref "R45") (pin "1") (pinfunction "1_1") (pintype "passive"))
      (node (ref "U6") (pin "15") (pinfunction "Q0_15") (pintype "power_in"))
    )
    (net (code "135") (name "/Q42") (class "Default")
      (node (ref "R46") (pin "1") (pinfunction "1_1") (pintype "passive"))
      (node (ref "U6") (pin "1") (pinfunction "Q1_1") (pintype "power_in"))
    )
    (net (code "136") (name "/Q43") (class "Default")
      (node (ref "R47") (pin "1") (pinfunction "1_1") (pintype "passive"))
      (node (ref "U6") (pin "2") (pinfunction "Q2_2") (pintype "power_in"))
    )
    (net (code "137") (name "/Q44") (class "Default")
      (node (ref "R48") (pin "1") (pinfunction "1_1") (pintype "passive"))
      (node (ref "U6") (pin "3") (pinfunction "Q3_3") (pintype "power_in"))
    )
    (net (code "138") (name "/Q45") (class "Default")
      (node (ref "R49") (pin "1") (pinfunction "1_1") (pintype "passive"))
      (node (ref "U6") (pin "4") (pinfunction "Q4_4") (pintype "power_in"))
    )
    (net (code "139") (name "/Q46") (class "Default")
      (node (ref "R50") (pin "1") (pinfunction "1_1") (pintype "passive"))
      (node (ref "U6") (pin "5") (pinfunction "Q5_5") (pintype "power_in"))
    )
    (net (code "140") (name "/Q47") (class "Default")
      (node (ref "R51") (pin "1") (pinfunction "1_1") (pintype "passive"))
      (node (ref "U6") (pin "6") (pinfunction "Q6_6") (pintype "power_in"))
    )
    (net (code "141") (name "/Q48") (class "Default")
      (node (ref "R52") (pin "1") (pinfunction "1_1") (pintype "passive"))
      (node (ref "U6") (pin "7") (pinfunction "Q7_7") (pintype "power_in"))
    )
    (net (code "142") (name "/Q49") (class "Default")
      (node (ref "U1") (pin "9") (pinfunction "SQH_9") (pintype "power_in"))
      (node (ref "U3") (pin "14") (pinfunction "SI__DS_14") (pintype "power_in"))
    )
    (net (code "144") (name "GND") (class "Default")
      (node (ref "C1") (pin "2") (pinfunction "2_2") (pintype "passive"))
      (node (ref "C2") (pin "2") (pinfunction "2_2") (pintype "passive"))
      (node (ref "C3") (pin "2") (pinfunction "2_2") (pintype "passive"))
      (node (ref "C4") (pin "2") (pinfunction "2_2") (pintype "passive"))
      (node (ref "C5") (pin "2") (pinfunction "2_2") (pintype "passive"))
      (node (ref "C6") (pin "2") (pinfunction "2_2") (pintype "passive"))
      (node (ref "LED1") (pin "2") (pinfunction "K_2") (pintype "passive"))
      (node (ref "LED2") (pin "2") (pinfunction "K_2") (pintype "passive"))
      (node (ref "LED3") (pin "2") (pinfunction "K_2") (pintype "passive"))
      (node (ref "LED4") (pin "2") (pinfunction "K_2") (pintype "passive"))
      (node (ref "Q1") (pin "2") (pinfunction "E_2") (pintype "passive"))
      (node (ref "Q10") (pin "2") (pinfunction "E_2") (pintype "passive"))
      (node (ref "Q11") (pin "2") (pinfunction "E_2") (pintype "passive"))
      (node (ref "Q12") (pin "2") (pinfunction "E_2") (pintype "passive"))
      (node (ref "Q13") (pin "2") (pinfunction "E_2") (pintype "passive"))
      (node (ref "Q14") (pin "2") (pinfunction "E_2") (pintype "passive"))
      (node (ref "Q15") (pin "2") (pinfunction "E_2") (pintype "passive"))
      (node (ref "Q16") (pin "2") (pinfunction "E_2") (pintype "passive"))
      (node (ref "Q17") (pin "2") (pinfunction "E_2") (pintype "passive"))
      (node (ref "Q18") (pin "2") (pinfunction "E_2") (pintype "passive"))
      (node (ref "Q19") (pin "2") (pinfunction "E_2") (pintype "passive"))
      (node (ref "Q2") (pin "2") (pinfunction "E_2") (pintype "passive"))
      (node (ref "Q20") (pin "2") (pinfunction "E_2") (pintype "passive"))
      (node (ref "Q21") (pin "2") (pinfunction "E_2") (pintype "passive"))
      (node (ref "Q22") (pin "2") (pinfunction "E_2") (pintype "passive"))
      (node (ref "Q23") (pin "2") (pinfunction "E_2") (pintype "passive"))
      (node (ref "Q24") (pin "2") (pinfunction "E_2") (pintype "passive"))
      (node (ref "Q25") (pin "2") (pinfunction "E_2") (pintype "passive"))
      (node (ref "Q26") (pin "2") (pinfunction "E_2") (pintype "passive"))
      (node (ref "Q27") (pin "2") (pinfunction "E_2") (pintype "passive"))
      (node (ref "Q28") (pin "2") (pinfunction "E_2") (pintype "passive"))
      (node (ref "Q29") (pin "2") (pinfunction "E_2") (pintype "passive"))
      (node (ref "Q3") (pin "2") (pinfunction "E_2") (pintype "passive"))
      (node (ref "Q30") (pin "2") (pinfunction "E_2") (pintype "passive"))
      (node (ref "Q31") (pin "2") (pinfunction "E_2") (pintype "passive"))
      (node (ref "Q32") (pin "2") (pinfunction "E_2") (pintype "passive"))
      (node (ref "Q33") (pin "2") (pinfunction "E_2") (pintype "passive"))
      (node (ref "Q34") (pin "2") (pinfunction "E_2") (pintype "passive"))
      (node (ref "Q35") (pin "2") (pinfunction "E_2") (pintype "passive"))
      (node (ref "Q36") (pin "2") (pinfunction "E_2") (pintype "passive"))
      (node (ref "Q37") (pin "2") (pinfunction "E_2") (pintype "passive"))
      (node (ref "Q38") (pin "2") (pinfunction "E_2") (pintype "passive"))
      (node (ref "Q39") (pin "2") (pinfunction "E_2") (pintype "passive"))
      (node (ref "Q4") (pin "2") (pinfunction "E_2") (pintype "passive"))
      (node (ref "Q40") (pin "2") (pinfunction "E_2") (pintype "passive"))
      (node (ref "Q41") (pin "2") (pinfunction "E_2") (pintype "passive"))
      (node (ref "Q42") (pin "2") (pinfunction "E_2") (pintype "passive"))
      (node (ref "Q43") (pin "2") (pinfunction "E_2") (pintype "passive"))
      (node (ref "Q44") (pin "2") (pinfunction "E_2") (pintype "passive"))
      (node (ref "Q46") (pin "2") (pinfunction "E_2") (pintype "passive"))
      (node (ref "Q5") (pin "2") (pinfunction "E_2") (pintype "passive"))
      (node (ref "Q6") (pin "2") (pinfunction "E_2") (pintype "passive"))
      (node (ref "Q7") (pin "2") (pinfunction "E_2") (pintype "passive"))
      (node (ref "Q8") (pin "2") (pinfunction "E_2") (pintype "passive"))
      (node (ref "Q9") (pin "2") (pinfunction "E_2") (pintype "passive"))
      (node (ref "U1") (pin "13") (pinfunction "OE_13") (pintype "power_in"))
      (node (ref "U1") (pin "8") (pinfunction "GND_8") (pintype "power_in"))
      (node (ref "U2") (pin "13") (pinfunction "OE_13") (pintype "power_in"))
      (node (ref "U2") (pin "8") (pinfunction "GND_8") (pintype "power_in"))
      (node (ref "U3") (pin "13") (pinfunction "OE_13") (pintype "power_in"))
      (node (ref "U3") (pin "8") (pinfunction "GND_8") (pintype "power_in"))
      (node (ref "U4") (pin "13") (pinfunction "OE_13") (pintype "power_in"))
      (node (ref "U4") (pin "8") (pinfunction "GND_8") (pintype "power_in"))
      (node (ref "U5") (pin "13") (pinfunction "OE_13") (pintype "power_in"))
      (node (ref "U5") (pin "8") (pinfunction "GND_8") (pintype "power_in"))
      (node (ref "U6") (pin "13") (pinfunction "OE_13") (pintype "power_in"))
      (node (ref "U6") (pin "8") (pinfunction "GND_8") (pintype "power_in"))
    )
    (net (code "145") (name "Net-(LED1-A)") (class "Default")
      (node (ref "LED1") (pin "1") (pinfunction "A_1") (pintype "passive"))
      (node (ref "R49") (pin "2") (pinfunction "2_2") (pintype "passive"))
    )
    (net (code "146") (name "Net-(LED2-A)") (class "Default")
      (node (ref "LED2") (pin "1") (pinfunction "A_1") (pintype "passive"))
      (node (ref "R50") (pin "2") (pinfunction "2_2") (pintype "passive"))
    )
    (net (code "147") (name "Net-(LED3-A)") (class "Default")
      (node (ref "LED3") (pin "1") (pinfunction "A_1") (pintype "passive"))
      (node (ref "R51") (pin "2") (pinfunction "2_2") (pintype "passive"))
    )
    (net (code "148") (name "Net-(LED4-A)") (class "Default")
      (node (ref "LED4") (pin "1") (pinfunction "A_1") (pintype "passive"))
      (node (ref "R52") (pin "2") (pinfunction "2_2") (pintype "passive"))
    )
    (net (code "149") (name "Net-(LED8-A)") (class "Default")
      (node (ref "LED8") (pin "1") (pinfunction "A_1") (pintype "passive"))
      (node (ref "R71") (pin "2") (pinfunction "2_2") (pintype "passive"))
    )
    (net (code "150") (name "Net-(LED8-K)") (class "Default")
      (node (ref "LED8") (pin "2") (pinfunction "K_2") (pintype "passive"))
      (node (ref "LED9") (pin "2") (pinfunction "K_2") (pintype "passive"))
      (node (ref "Q46") (pin "3") (pinfunction "C_3") (pintype "passive"))
    )
    (net (code "151") (name "Net-(LED9-A)") (class "Default")
      (node (ref "LED9") (pin "1") (pinfunction "A_1") (pintype "passive"))
      (node (ref "R72") (pin "2") (pinfunction "2_2") (pintype "passive"))
    )
    (net (code "152") (name "Net-(NX1-1)") (class "Default")
      (node (ref "NX1") (pin "2") (pinfunction "1_2") (pintype "passive"))
      (node (ref "R1") (pin "1") (pinfunction "1_1") (pintype "passive"))
    )
    (net (code "153") (name "Net-(NX2-1)") (class "Default")
      (node (ref "NX2") (pin "2") (pinfunction "1_2") (pintype "passive"))
      (node (ref "R13") (pin "1") (pinfunction "1_1") (pintype "passive"))
    )
    (net (code "154") (name "Net-(NX3-1)") (class "Default")
      (node (ref "NX3") (pin "2") (pinfunction "1_2") (pintype "passive"))
      (node (ref "R25") (pin "1") (pinfunction "1_1") (pintype "passive"))
    )
    (net (code "155") (name "Net-(NX4-1)") (class "Default")
      (node (ref "NX4") (pin "2") (pinfunction "1_2") (pintype "passive"))
      (node (ref "R37") (pin "1") (pinfunction "1_1") (pintype "passive"))
    )
    (net (code "156") (name "Net-(Q46-B)") (class "Default")
      (node (ref "Q46") (pin "1") (pinfunction "B_1") (pintype "passive"))
      (node (ref "R73") (pin "2") (pinfunction "2_2") (pintype "passive"))
    )
    (net (code "157") (name "Net-(U2-SI__DS)") (class "Default")
      (node (ref "U2") (pin "14") (pinfunction "SI__DS_14") (pintype "power_in"))
      (node (ref "U5") (pin "9") (pinfunction "SQH_9") (pintype "power_in"))
    )
    (net (code "158") (name "Net-(U2-SQH)") (class "Default")
      (node (ref "U2") (pin "9") (pinfunction "SQH_9") (pintype "power_in"))
      (node (ref "U4") (pin "14") (pinfunction "SI__DS_14") (pintype "power_in"))
    )
    (net (code "159") (name "Net-(U3-SQH)") (class "Default")
      (node (ref "U3") (pin "9") (pinfunction "SQH_9") (pintype "power_in"))
      (node (ref "U5") (pin "14") (pinfunction "SI__DS_14") (pintype "power_in"))
    )
    (net (code "160") (name "Net-(U4-SQH)") (class "Default")
      (node (ref "U4") (pin "9") (pinfunction "SQH_9") (pintype "power_in"))
      (node (ref "U6") (pin "14") (pinfunction "SI__DS_14") (pintype "power_in"))
    )
    (net (code "161") (name "VCC_3V3") (class "Default")
      (node (ref "C1") (pin "1") (pinfunction "1_1") (pintype "passive"))
      (node (ref "C2") (pin "1") (pinfunction "1_1") (pintype "passive"))
      (node (ref "C3") (pin "1") (pinfunction "1_1") (pintype "passive"))
      (node (ref "C4") (pin "1") (pinfunction "1_1") (pintype "passive"))
      (node (ref "C5") (pin "1") (pinfunction "1_1") (pintype "passive"))
      (node (ref "C6") (pin "1") (pinfunction "1_1") (pintype "passive"))
      (node (ref "U1") (pin "10") (pinfunction "SCLR_10") (pintype "power_in"))
      (node (ref "U1") (pin "16") (pinfunction "VCC_16") (pintype "passive"))
      (node (ref "U2") (pin "10") (pinfunction "SCLR_10") (pintype "power_in"))
      (node (ref "U2") (pin "16") (pinfunction "VCC_16") (pintype "passive"))
      (node (ref "U3") (pin "10") (pinfunction "SCLR_10") (pintype "power_in"))
      (node (ref "U3") (pin "16") (pinfunction "VCC_16") (pintype "passive"))
      (node (ref "U4") (pin "10") (pinfunction "SCLR_10") (pintype "power_in"))
      (node (ref "U4") (pin "16") (pinfunction "VCC_16") (pintype "passive"))
      (node (ref "U5") (pin "10") (pinfunction "SCLR_10") (pintype "power_in"))
      (node (ref "U5") (pin "16") (pinfunction "VCC_16") (pintype "passive"))
      (node (ref "U6") (pin "10") (pinfunction "SCLR_10") (pintype "power_in"))
      (node (ref "U6") (pin "16") (pinfunction "VCC_16") (pintype "passive"))
    )
    (net (code "162") (name "VCC_5V0") (class "Default")
      (node (ref "R71") (pin "1") (pinfunction "1_1") (pintype "passive"))
      (node (ref "R72") (pin "1") (pinfunction "1_1") (pintype "passive"))
    )
    (net (code "163") (name "VCC_170V") (class "Default")
      (node (ref "R1") (pin "2") (pinfunction "2_2") (pintype "passive"))
      (node (ref "R13") (pin "2") (pinfunction "2_2") (pintype "passive"))
      (node (ref "R25") (pin "2") (pinfunction "2_2") (pintype "passive"))
      (node (ref "R37") (pin "2") (pinfunction "2_2") (pintype "passive"))
    )
    (net (code "164") (name "unconnected-(U6-SQH-Pad9)") (class "Default")
      (node (ref "U6") (pin "9") (pinfunction "SQH_9") (pintype "power_in"))
    )
  )
)
